# V3.net
KiCad netlist of a schematic drawn in Altium Designer
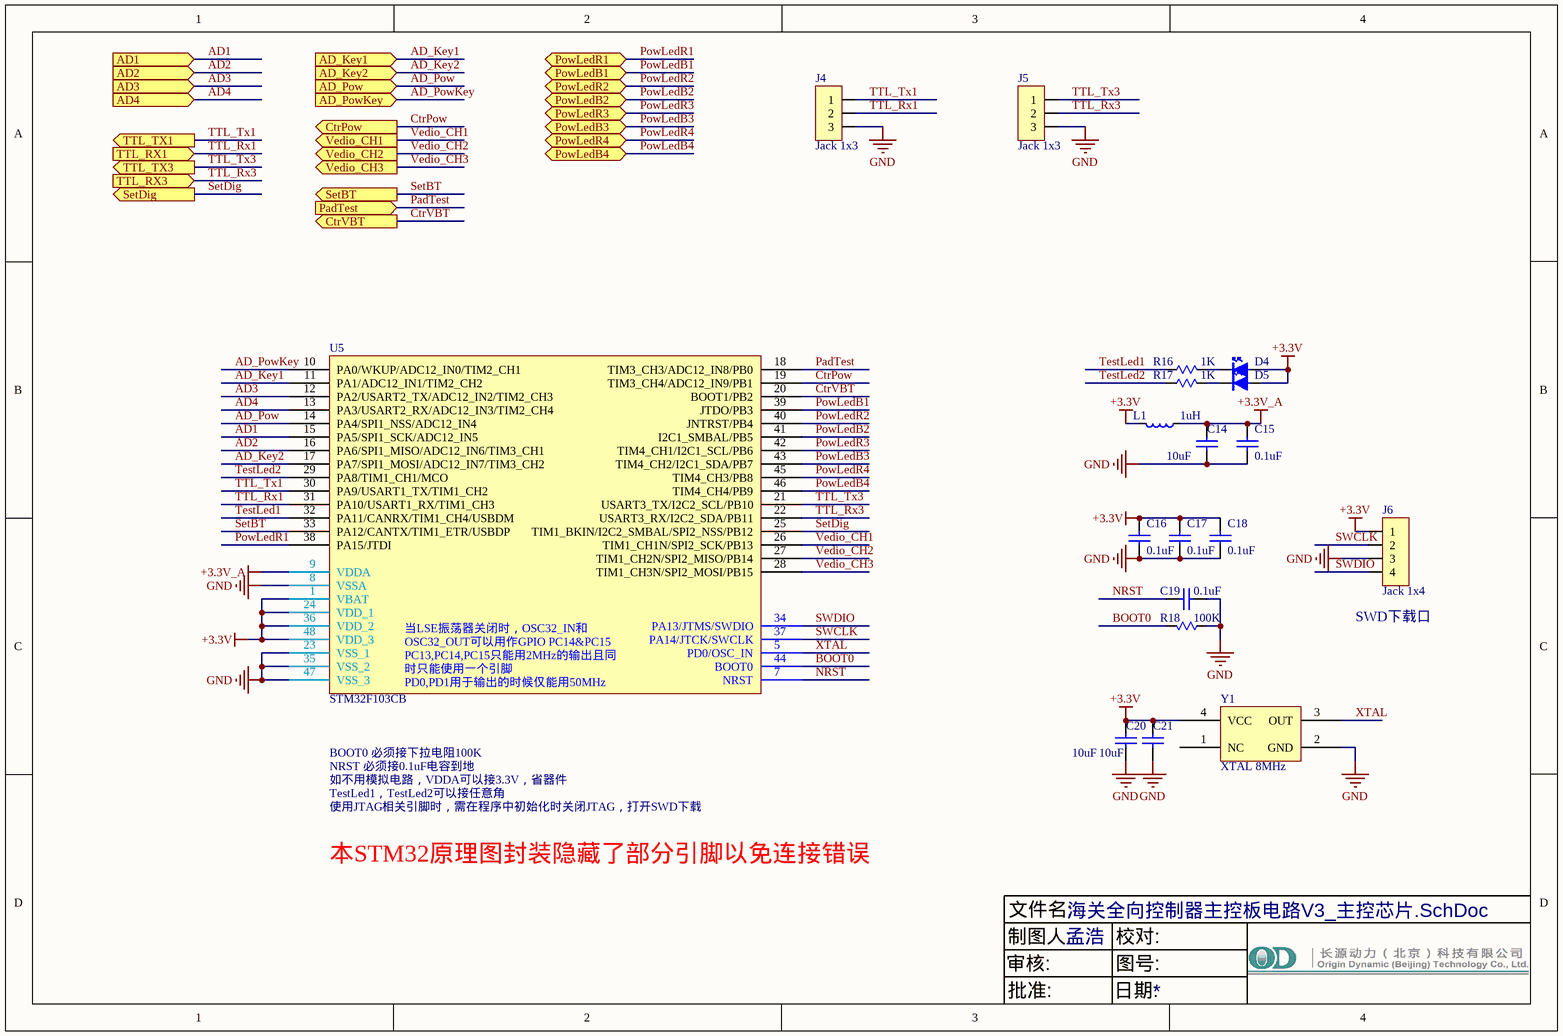
[diagram p0: 海关全向控制器主控板电路V3_主控芯片.SchDoc]

(export (version "E")
  (design (tool "Eeschema 10.0.6"))
  (components
    (comp (ref "C14")
      (value "10uF")
      (footprint "C0805")
      (description "Capacitor")
      (fields (field (name "PUBLISHER") "Altium Limited"))
      (libsource (lib "Miscellaneous Devices") (part "Cap"))
    )
    (comp (ref "C15")
      (value "0.1uF")
      (footprint "C0805")
      (description "Capacitor")
      (fields (field (name "PUBLISHER") "Altium Limited"))
      (libsource (lib "Miscellaneous Devices") (part "Cap"))
    )
    (comp (ref "C16")
      (value "0.1uF")
      (footprint "C0805")
      (description "Capacitor")
      (fields (field (name "PUBLISHER") "Altium Limited"))
      (libsource (lib "Miscellaneous Devices") (part "Cap"))
    )
    (comp (ref "C17")
      (value "0.1uF")
      (footprint "C0805")
      (description "Capacitor")
      (fields (field (name "PUBLISHER") "Altium Limited"))
      (libsource (lib "Miscellaneous Devices") (part "Cap"))
    )
    (comp (ref "C18")
      (value "0.1uF")
      (footprint "C0805")
      (description "Capacitor")
      (fields (field (name "PUBLISHER") "Altium Limited"))
      (libsource (lib "Miscellaneous Devices") (part "Cap"))
    )
    (comp (ref "C19")
      (value "0.1uF")
      (footprint "C0805")
      (description "Capacitor")
      (fields (field (name "PUBLISHER") "Altium Limited"))
      (libsource (lib "Miscellaneous Devices") (part "Cap"))
    )
    (comp (ref "C20")
      (value "10uF")
      (footprint "C0805")
      (description "Capacitor")
      (fields (field (name "PUBLISHER") "Altium Limited"))
      (libsource (lib "Miscellaneous Devices") (part "Cap"))
    )
    (comp (ref "C21")
      (value "10uF")
      (footprint "C0805")
      (description "Capacitor")
      (fields (field (name "PUBLISHER") "Altium Limited"))
      (libsource (lib "Miscellaneous Devices") (part "Cap"))
    )
    (comp (ref "D4")
      (value "LED")
      (footprint "LED0603")
      (libsource (lib "Passive Components Class") (part "LED"))
    )
    (comp (ref "D5")
      (value "LED")
      (footprint "LED0603")
      (libsource (lib "Passive Components Class") (part "LED"))
    )
    (comp (ref "J4")
      (value "Jack 1x3")
      (footprint "Jk1*3-2.0")
      (description "插座")
      (libsource (lib "Connector") (part "Jack 1x3"))
    )
    (comp (ref "J5")
      (value "Jack 1x3")
      (footprint "Jk1*3-2.0")
      (description "插座")
      (libsource (lib "Connector") (part "Jack 1x3"))
    )
    (comp (ref "J6")
      (value "Jack 1x4")
      (footprint "Jk1*4-2.0")
      (description "插座")
      (libsource (lib "Connector") (part "Jack 1x4"))
    )
    (comp (ref "L1")
      (value "1uH")
      (footprint "L0805")
      (description "INDUCTOR")
      (fields (field (name "PUBLISHER") "Altium Limited"))
      (libsource (lib "Passive Components Class") (part "INDUCTOR"))
    )
    (comp (ref "R16")
      (value "1K")
      (footprint "R0805")
      (description "Resistor")
      (fields (field (name "PUBLISHER") "Altium Limited"))
      (libsource (lib "UP-Robot") (part "Res"))
    )
    (comp (ref "R17")
      (value "1K")
      (footprint "R0805")
      (description "Resistor")
      (fields (field (name "PUBLISHER") "Altium Limited"))
      (libsource (lib "UP-Robot") (part "Res"))
    )
    (comp (ref "R18")
      (value "100K")
      (footprint "R0805")
      (description "Resistor")
      (fields (field (name "PUBLISHER") "Altium Limited"))
      (libsource (lib "Passive Components Class") (part "RES"))
    )
    (comp (ref "U5") (value "STM32F103CB") (footprint "LQF48") (libsource (lib "stm32") (part "STM32F103Cx")))
    (comp (ref "Y1") (value "XTAL 8MHz") (footprint "XTAL5032") (libsource (lib "Mic2805") (part "XTAL")))
  )
  (nets
    (net (code "1") (name "+3.3V") (class "Default")
      (node (ref "C16") (pin "1") (pinfunction "1_1") (pintype "passive"))
      (node (ref "C17") (pin "1") (pinfunction "1_1") (pintype "passive"))
      (node (ref "C18") (pin "1") (pinfunction "1_1") (pintype "passive"))
      (node (ref "C20") (pin "2") (pinfunction "2_2") (pintype "passive"))
      (node (ref "C21") (pin "2") (pinfunction "2_2") (pintype "passive"))
      (node (ref "D4") (pin "1") (pinfunction "A_1") (pintype "passive"))
      (node (ref "D5") (pin "1") (pinfunction "A_1") (pintype "passive"))
      (node (ref "J6") (pin "1") (pinfunction "1_1") (pintype "passive"))
      (node (ref "L1") (pin "1") (pinfunction "1_1") (pintype "passive"))
      (node (ref "U5") (pin "1") (pinfunction "VBAT_1") (pintype "power_in"))
      (node (ref "U5") (pin "24") (pinfunction "VDD_1_24") (pintype "power_in"))
      (node (ref "U5") (pin "36") (pinfunction "VDD_2_36") (pintype "power_in"))
      (node (ref "U5") (pin "48") (pinfunction "VDD_3_48") (pintype "power_in"))
      (node (ref "Y1") (pin "4") (pinfunction "VCC_4") (pintype "passive"))
    )
    (net (code "2") (name "+3.3V_A") (class "Default")
      (node (ref "C14") (pin "2") (pinfunction "2_2") (pintype "passive"))
      (node (ref "C15") (pin "1") (pinfunction "1_1") (pintype "passive"))
      (node (ref "L1") (pin "2") (pinfunction "2_2") (pintype "passive"))
      (node (ref "U5") (pin "9") (pinfunction "VDDA_9") (pintype "power_in"))
    )
    (net (code "3") (name "/AD1") (class "Default")
      (node (ref "U5") (pin "15") (pinfunction "PA5/SPI1_SCK/ADC12_IN5_15") (pintype "passive"))
    )
    (net (code "4") (name "/AD2") (class "Default")
      (node (ref "U5") (pin "16") (pinfunction "PA6/SPI1_MISO/ADC12_IN6/TIM3_CH1_16") (pintype "passive"))
    )
    (net (code "5") (name "/AD3") (class "Default")
      (node (ref "U5") (pin "12") (pinfunction "PA2/USART2_TX/ADC12_IN2/TIM2_CH3_12") (pintype "passive"))
    )
    (net (code "6") (name "/AD4") (class "Default")
      (node (ref "U5") (pin "13") (pinfunction "PA3/USART2_RX/ADC12_IN3/TIM2_CH4_13") (pintype "passive"))
    )
    (net (code "7") (name "/AD_Key1") (class "Default")
      (node (ref "U5") (pin "11") (pinfunction "PA1/ADC12_IN1/TIM2_CH2_11") (pintype "passive"))
    )
    (net (code "8") (name "/AD_Key2") (class "Default")
      (node (ref "U5") (pin "17") (pinfunction "PA7/SPI1_MOSI/ADC12_IN7/TIM3_CH2_17") (pintype "passive"))
    )
    (net (code "9") (name "/AD_Pow") (class "Default")
      (node (ref "U5") (pin "14") (pinfunction "PA4/SPI1_NSS/ADC12_IN4_14") (pintype "passive"))
    )
    (net (code "10") (name "/AD_PowKey") (class "Default")
      (node (ref "U5") (pin "10") (pinfunction "PA0/WKUP/ADC12_IN0/TIM2_CH1_10") (pintype "passive"))
    )
    (net (code "11") (name "/BOOT0") (class "Default")
      (node (ref "R18") (pin "2") (pinfunction "2_2") (pintype "passive"))
      (node (ref "U5") (pin "44") (pinfunction "BOOT0_44") (pintype "passive"))
    )
    (net (code "12") (name "/CtrPow") (class "Default")
      (node (ref "U5") (pin "19") (pinfunction "TIM3_CH4/ADC12_IN9/PB1_19") (pintype "passive"))
    )
    (net (code "13") (name "/CtrVBT") (class "Default")
      (node (ref "U5") (pin "20") (pinfunction "BOOT1/PB2_20") (pintype "passive"))
    )
    (net (code "14") (name "/NRST") (class "Default")
      (node (ref "C19") (pin "1") (pinfunction "1_1") (pintype "passive"))
      (node (ref "U5") (pin "7") (pinfunction "NRST_7") (pintype "passive"))
    )
    (net (code "15") (name "/PadTest") (class "Default")
      (node (ref "U5") (pin "18") (pinfunction "TIM3_CH3/ADC12_IN8/PB0_18") (pintype "passive"))
    )
    (net (code "16") (name "/PowLedB1") (class "Default")
      (node (ref "U5") (pin "39") (pinfunction "JTDO/PB3_39") (pintype "passive"))
    )
    (net (code "17") (name "/PowLedB2") (class "Default")
      (node (ref "U5") (pin "41") (pinfunction "I2C1_SMBAL/PB5_41") (pintype "passive"))
    )
    (net (code "18") (name "/PowLedB3") (class "Default")
      (node (ref "U5") (pin "43") (pinfunction "TIM4_CH2/I2C1_SDA/PB7_43") (pintype "passive"))
    )
    (net (code "19") (name "/PowLedB4") (class "Default")
      (node (ref "U5") (pin "46") (pinfunction "TIM4_CH4/PB9_46") (pintype "passive"))
    )
    (net (code "20") (name "/PowLedR1") (class "Default")
      (node (ref "U5") (pin "38") (pinfunction "PA15/JTDI_38") (pintype "passive"))
    )
    (net (code "21") (name "/PowLedR2") (class "Default")
      (node (ref "U5") (pin "40") (pinfunction "JNTRST/PB4_40") (pintype "passive"))
    )
    (net (code "22") (name "/PowLedR3") (class "Default")
      (node (ref "U5") (pin "42") (pinfunction "TIM4_CH1/I2C1_SCL/PB6_42") (pintype "passive"))
    )
    (net (code "23") (name "/PowLedR4") (class "Default")
      (node (ref "U5") (pin "45") (pinfunction "TIM4_CH3/PB8_45") (pintype "passive"))
    )
    (net (code "24") (name "/SWCLK") (class "Default")
      (node (ref "J6") (pin "2") (pinfunction "2_2") (pintype "passive"))
      (node (ref "U5") (pin "37") (pinfunction "PA14/JTCK/SWCLK_37") (pintype "passive"))
    )
    (net (code "25") (name "/SWDIO") (class "Default")
      (node (ref "J6") (pin "4") (pinfunction "4_4") (pintype "passive"))
      (node (ref "U5") (pin "34") (pinfunction "PA13/JTMS/SWDIO_34") (pintype "passive"))
    )
    (net (code "26") (name "/SetBT") (class "Default")
      (node (ref "U5") (pin "33") (pinfunction "PA12/CANTX/TIM1_ETR/USBDP_33") (pintype "passive"))
    )
    (net (code "27") (name "/SetDig") (class "Default")
      (node (ref "U5") (pin "25") (pinfunction "TIM1_BKIN/I2C2_SMBAL/SPI2_NSS/PB12_25") (pintype "passive"))
    )
    (net (code "28") (name "/TTL_Rx1") (class "Default")
      (node (ref "J4") (pin "2") (pinfunction "2_2") (pintype "passive"))
      (node (ref "U5") (pin "31") (pinfunction "PA10/USART1_RX/TIM1_CH3_31") (pintype "passive"))
    )
    (net (code "29") (name "/TTL_Rx3") (class "Default")
      (node (ref "J5") (pin "2") (pinfunction "2_2") (pintype "passive"))
      (node (ref "U5") (pin "22") (pinfunction "USART3_RX/I2C2_SDA/PB11_22") (pintype "passive"))
    )
    (net (code "30") (name "/TTL_Tx1") (class "Default")
      (node (ref "J4") (pin "1") (pinfunction "1_1") (pintype "passive"))
      (node (ref "U5") (pin "30") (pinfunction "PA9/USART1_TX/TIM1_CH2_30") (pintype "passive"))
    )
    (net (code "31") (name "/TTL_Tx3") (class "Default")
      (node (ref "J5") (pin "1") (pinfunction "1_1") (pintype "passive"))
      (node (ref "U5") (pin "21") (pinfunction "USART3_TX/I2C2_SCL/PB10_21") (pintype "passive"))
    )
    (net (code "32") (name "/TestLed1") (class "Default")
      (node (ref "R16") (pin "1") (pinfunction "1_1") (pintype "passive"))
      (node (ref "U5") (pin "32") (pinfunction "PA11/CANRX/TIM1_CH4/USBDM_32") (pintype "passive"))
    )
    (net (code "33") (name "/TestLed2") (class "Default")
      (node (ref "R17") (pin "1") (pinfunction "1_1") (pintype "passive"))
      (node (ref "U5") (pin "29") (pinfunction "PA8/TIM1_CH1/MCO_29") (pintype "passive"))
    )
    (net (code "34") (name "/Vedio_CH1") (class "Default")
      (node (ref "U5") (pin "26") (pinfunction "TIM1_CH1N/SPI2_SCK/PB13_26") (pintype "passive"))
    )
    (net (code "35") (name "/Vedio_CH2") (class "Default")
      (node (ref "U5") (pin "27") (pinfunction "TIM1_CH2N/SPI2_MISO/PB14_27") (pintype "passive"))
    )
    (net (code "36") (name "/Vedio_CH3") (class "Default")
      (node (ref "U5") (pin "28") (pinfunction "TIM1_CH3N/SPI2_MOSI/PB15_28") (pintype "passive"))
    )
    (net (code "37") (name "/XTAL") (class "Default")
      (node (ref "U5") (pin "5") (pinfunction "PD0/OSC_IN_5") (pintype "passive"))
      (node (ref "Y1") (pin "3") (pinfunction "OUT_3") (pintype "passive"))
    )
    (net (code "38") (name "GND") (class "Default")
      (node (ref "C14") (pin "1") (pinfunction "1_1") (pintype "passive"))
      (node (ref "C15") (pin "2") (pinfunction "2_2") (pintype "passive"))
      (node (ref "C16") (pin "2") (pinfunction "2_2") (pintype "passive"))
      (node (ref "C17") (pin "2") (pinfunction "2_2") (pintype "passive"))
      (node (ref "C18") (pin "2") (pinfunction "2_2") (pintype "passive"))
      (node (ref "C19") (pin "2") (pinfunction "2_2") (pintype "passive"))
      (node (ref "C20") (pin "1") (pinfunction "1_1") (pintype "passive"))
      (node (ref "C21") (pin "1") (pinfunction "1_1") (pintype "passive"))
      (node (ref "J4") (pin "3") (pinfunction "3_3") (pintype "passive"))
      (node (ref "J5") (pin "3") (pinfunction "3_3") (pintype "passive"))
      (node (ref "J6") (pin "3") (pinfunction "3_3") (pintype "passive"))
      (node (ref "R18") (pin "1") (pinfunction "1_1") (pintype "passive"))
      (node (ref "U5") (pin "23") (pinfunction "VSS_1_23") (pintype "power_in"))
      (node (ref "U5") (pin "35") (pinfunction "VSS_2_35") (pintype "power_in"))
      (node (ref "U5") (pin "47") (pinfunction "VSS_3_47") (pintype "power_in"))
      (node (ref "U5") (pin "8") (pinfunction "VSSA_8") (pintype "power_in"))
      (node (ref "Y1") (pin "2") (pinfunction "GND_2") (pintype "passive"))
    )
    (net (code "39") (name "Net-(D4-K)") (class "Default")
      (node (ref "D4") (pin "2") (pinfunction "K_2") (pintype "passive"))
      (node (ref "R16") (pin "2") (pinfunction "2_2") (pintype "passive"))
    )
    (net (code "40") (name "Net-(D5-K)") (class "Default")
      (node (ref "D5") (pin "2") (pinfunction "K_2") (pintype "passive"))
      (node (ref "R17") (pin "2") (pinfunction "2_2") (pintype "passive"))
    )
    (net (code "41") (name "unconnected-(U5-PC13-TAMPER-RTC-Pad2)") (class "Default")
      (node (ref "U5") (pin "2") (pinfunction "PC13-TAMPER-RTC_2") (pintype "passive"))
    )
    (net (code "42") (name "unconnected-(U5-PC14-OSC32_IN-Pad3)") (class "Default")
      (node (ref "U5") (pin "3") (pinfunction "PC14-OSC32_IN_3") (pintype "passive"))
    )
    (net (code "43") (name "unconnected-(U5-PC15-OSC32_OUT-Pad4)") (class "Default")
      (node (ref "U5") (pin "4") (pinfunction "PC15-OSC32_OUT_4") (pintype "passive"))
    )
    (net (code "44") (name "unconnected-(U5-PD1{slash}OSC_OUT-Pad6)") (class "Default")
      (node (ref "U5") (pin "6") (pinfunction "PD1/OSC_OUT_6") (pintype "passive"))
    )
    (net (code "45") (name "unconnected-(Y1-NC-Pad1)") (class "Default")
      (node (ref "Y1") (pin "1") (pinfunction "NC_1") (pintype "passive"))
    )
  )
)
